# GSM_Stat_LED_Driver.net
KiCad netlist of a schematic drawn in Altium Designer
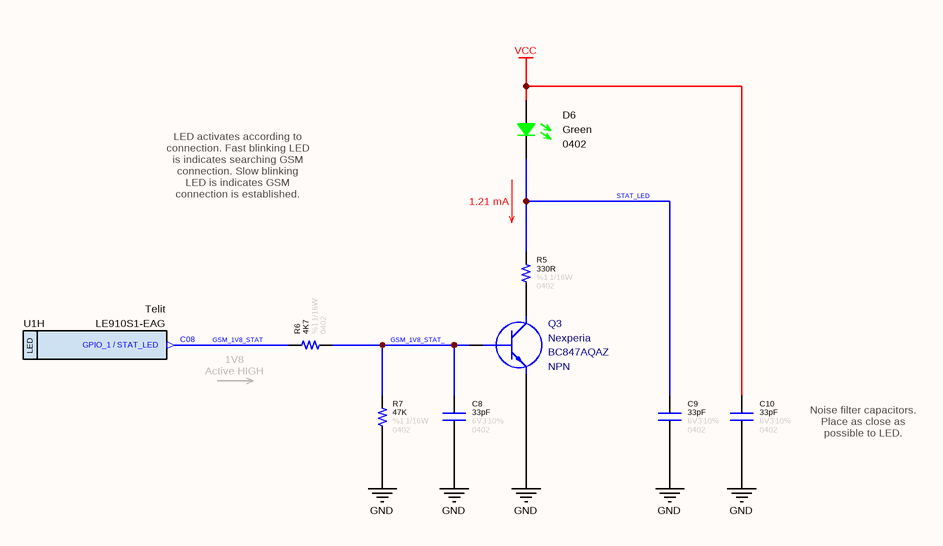
[diagram p0: GSM Stat LED Driver.SchDoc]

(export (version "E")
  (design (tool "Eeschema 10.0.6"))
  (components
    (comp (ref "C8")
      (value "33pF")
      (footprint "CAPACITOR_0402")
      (description "Capacitor - 33pF [0402] (Ceramic)")
      (fields
        (field (name "MANUFACTURER PART NUMBER") "C0402C330J9RACAUTO")
        (field (name "TOLERANCE") "10%")
        (field (name "CASE") "0402")
        (field (name "VOLTAGE") "6V3")
      )
      (libsource (lib "P101DA_Library") (part "Capacitor - 33pF [0402-6V3]"))
    )
    (comp (ref "C9")
      (value "33pF")
      (footprint "CAPACITOR_0402")
      (description "Capacitor - 33pF [0402] (Ceramic)")
      (fields
        (field (name "MANUFACTURER PART NUMBER") "C0402C330J9RACAUTO")
        (field (name "TOLERANCE") "10%")
        (field (name "CASE") "0402")
        (field (name "VOLTAGE") "6V3")
      )
      (libsource (lib "P101DA_Library") (part "Capacitor - 33pF [0402-6V3]"))
    )
    (comp (ref "C10")
      (value "33pF")
      (footprint "CAPACITOR_0402")
      (description "Capacitor - 33pF [0402] (Ceramic)")
      (fields
        (field (name "MANUFACTURER PART NUMBER") "C0402C330J9RACAUTO")
        (field (name "TOLERANCE") "10%")
        (field (name "CASE") "0402")
        (field (name "VOLTAGE") "6V3")
      )
      (libsource (lib "P101DA_Library") (part "Capacitor - 33pF [0402-6V3]"))
    )
    (comp (ref "D6")
      (value "SMD LED (Green)")
      (footprint "LED_0402")
      (description "Standard LEDs - SMD MINI-MOLD ULTRA COMPACT GREEN")
      (fields
        (field (name "MANUFACTURER PART NUMBER") "SML-P12MTT86R")
        (field (name "CASE") "0402")
        (field (name "COLOR") "Green")
      )
      (libsource (lib "P101DA_Library") (part "Diode - LED (0402-Green)"))
    )
    (comp (ref "Q3")
      (value "BC847AQAZ")
      (footprint "SOT1215")
      (description "Bipolar NPN Transistors")
      (fields
        (field (name "MANUFACTURER NAME") "Nexperia")
        (field (name "MANUFACTURER PART NUMBER") "BC847AQAZ")
        (field (name "POLARITY") "NPN")
      )
      (libsource (lib "P101DA_Library") (part "Transistor - BC847"))
    )
    (comp (ref "R5")
      (value "330R")
      (footprint "RESISTOR_0402")
      (description "Thick Film Resistors - SMD 1/16 W 330 Ohm 1%")
      (fields
        (field (name "MANUFACTURER PART NUMBER") "CRCW0402330RFKED")
        (field (name "CASE") "0402")
        (field (name "TOLERANCE") "%1")
        (field (name "POWER") "1/16W")
        (field (name "Comment") "330R - 0402 - %1 - 1/16W")
      )
      (libsource (lib "P101DA_Library") (part "Resistor - 330R [0402]"))
    )
    (comp (ref "R6")
      (value "4K7")
      (footprint "RESISTOR_0402")
      (description "Thick Film Resistors - SMD 1/16 W 4.7 KOhm 1%")
      (fields
        (field (name "MANUFACTURER PART NUMBER") "CRCW04024K70FKED")
        (field (name "TOLERANCE") "%1")
        (field (name "CASE") "0402")
        (field (name "POWER") "1/16W")
        (field (name "Comment") "4K7 - 0402 - %1 - 1/16W")
      )
      (libsource (lib "P101DA_Library") (part "Resistor - 4K7 [0402]"))
    )
    (comp (ref "R7")
      (value "47K")
      (footprint "RESISTOR_0402")
      (description "Thick Film Resistors - SMD 1/16 W 47 KOhm 1%")
      (fields
        (field (name "MANUFACTURER PART NUMBER") "CRCW040247K0FKED")
        (field (name "TOLERANCE") "%1")
        (field (name "CASE") "0402")
        (field (name "POWER") "1/16W")
        (field (name "Comment") "47K - 0402 - %1 - 1/16W")
      )
      (libsource (lib "P101DA_Library") (part "Resistor - 47K [0402]"))
    )
    (comp (ref "U1")
      (value "LE910S1-EAG LTE GSM Module")
      (footprint "LE910 GSM Modem")
      (description "Telit LE910S1-EAG GPRS/GNSS Module")
      (fields
        (field (name "MANUFACTURER PART NUMBER") "LE910S1-EAG")
        (field (name "MANUFACTURER NAME") "Telit")
      )
      (libsource (lib "P101DA_Library") (part "IC - LE910S1-EAG"))
    )
  )
  (nets
    (net (code "1") (name "/GSM_1V8_STAT") (class "Default")
      (node (ref "R6") (pin "2") (pinfunction "2_2") (pintype "passive"))
      (node (ref "U1") (pin "C08") (pinfunction "GPIO_1_/_STAT_LED_C08") (pintype "output"))
    )
    (net (code "2") (name "/GSM_1V8_STAT_") (class "Default")
      (node (ref "C8") (pin "2") (pinfunction "2_2") (pintype "passive"))
      (node (ref "Q3") (pin "1") (pinfunction "B_1") (pintype "passive"))
      (node (ref "R6") (pin "1") (pinfunction "1_1") (pintype "passive"))
      (node (ref "R7") (pin "2") (pinfunction "2_2") (pintype "passive"))
    )
    (net (code "3") (name "/STAT_LED") (class "Default")
      (node (ref "C9") (pin "2") (pinfunction "2_2") (pintype "passive"))
      (node (ref "D6") (pin "1") (pinfunction "1_1") (pintype "passive"))
      (node (ref "R5") (pin "2") (pinfunction "2_2") (pintype "passive"))
    )
    (net (code "4") (name "GND") (class "Default")
      (node (ref "C10") (pin "1") (pinfunction "1_1") (pintype "passive"))
      (node (ref "C8") (pin "1") (pinfunction "1_1") (pintype "passive"))
      (node (ref "C9") (pin "1") (pinfunction "1_1") (pintype "passive"))
      (node (ref "Q3") (pin "2") (pinfunction "E_2") (pintype "passive"))
      (node (ref "R7") (pin "1") (pinfunction "1_1") (pintype "passive"))
    )
    (net (code "5") (name "Net-(Q3-C)") (class "Default")
      (node (ref "Q3") (pin "3") (pinfunction "C_3") (pintype "passive"))
      (node (ref "R5") (pin "1") (pinfunction "1_1") (pintype "passive"))
    )
    (net (code "6") (name "VCC") (class "Default")
      (node (ref "C10") (pin "2") (pinfunction "2_2") (pintype "passive"))
      (node (ref "D6") (pin "2") (pinfunction "2_2") (pintype "passive"))
    )
  )
)
